# chassis_board.net
KiCad netlist of a schematic drawn in EAGLE
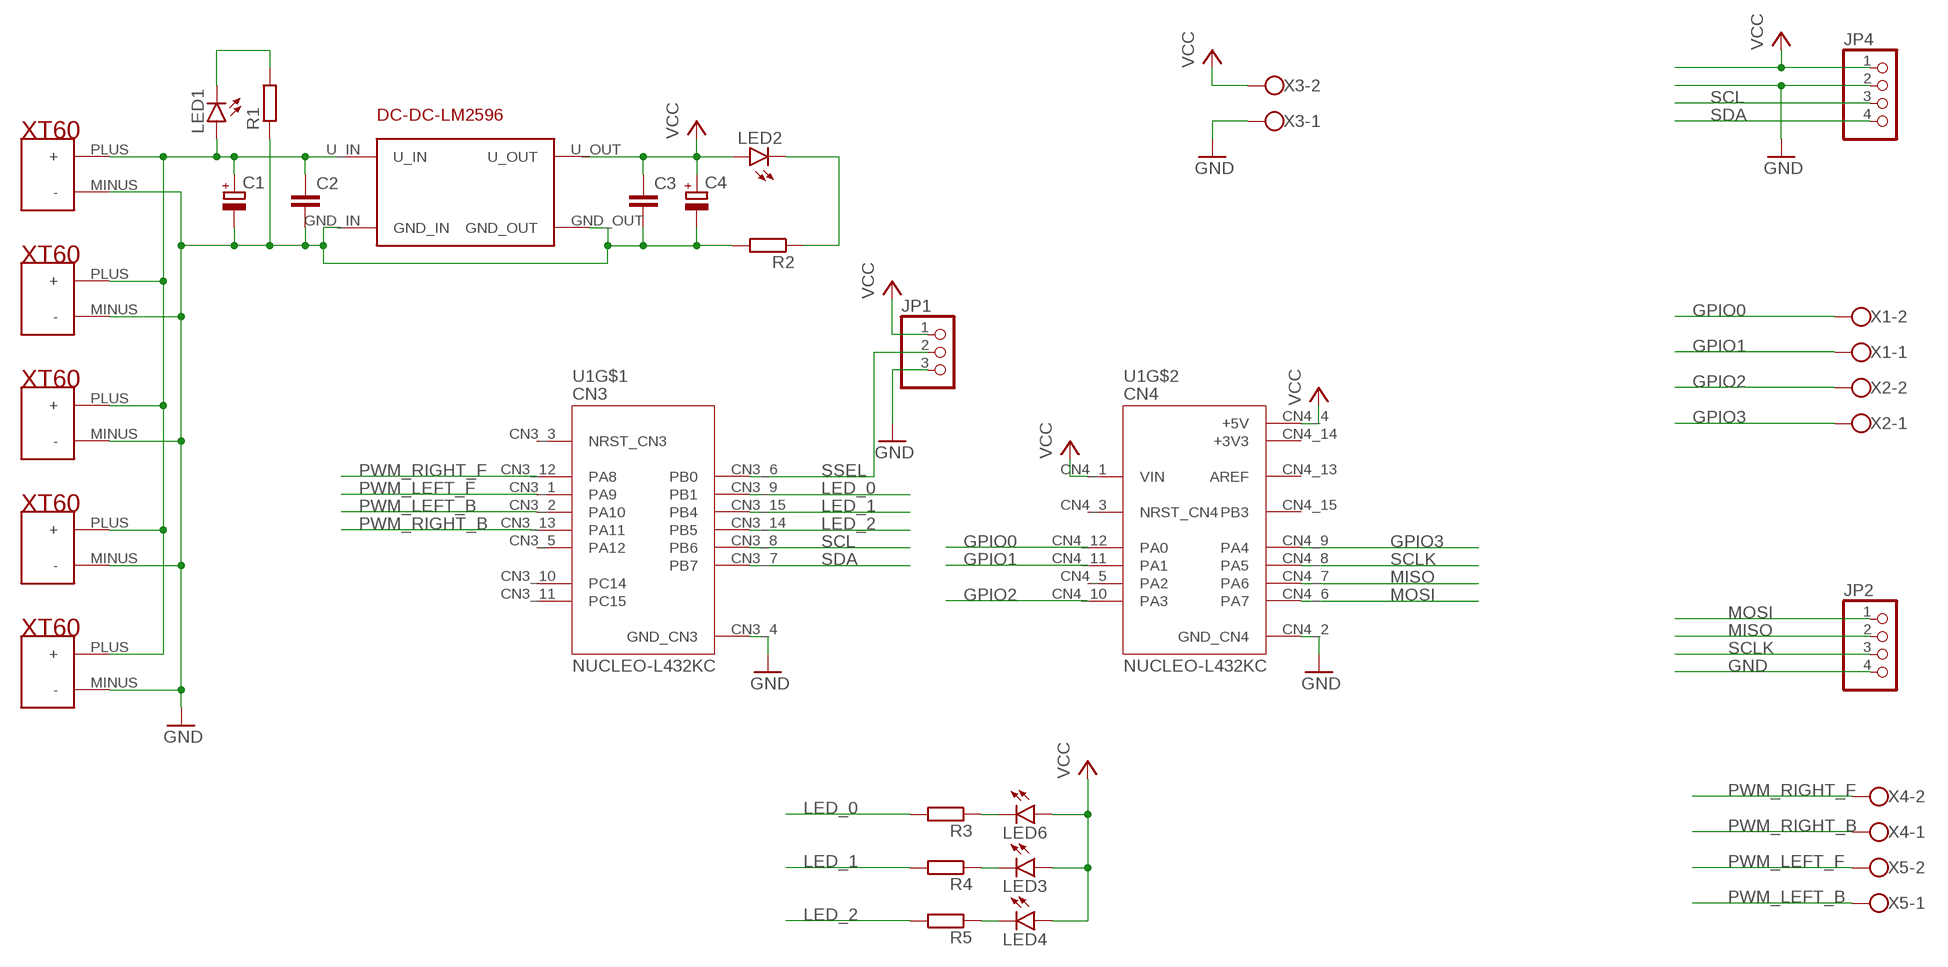
[diagram p0: schematic, sheet 1]

(export (version "E")
  (design (tool "Eeschema 10.0.6"))
  (components
    (comp (ref "C1")
      (value "CPOL-EU140CLH-0810")
      (footprint "eagle-import:140CLH-0810")
      (libsource (lib "eagle-import") (part "CPOL-EU140CLH-0810"))
    )
    (comp (ref "C2")
      (value "C-EUC1206")
      (footprint "eagle-import:C1206")
      (libsource (lib "eagle-import") (part "C-EUC1206"))
    )
    (comp (ref "C3")
      (value "C-EUC1206")
      (footprint "eagle-import:C1206")
      (libsource (lib "eagle-import") (part "C-EUC1206"))
    )
    (comp (ref "C4")
      (value "CPOL-EU140CLH-0810")
      (footprint "eagle-import:140CLH-0810")
      (libsource (lib "eagle-import") (part "CPOL-EU140CLH-0810"))
    )
    (comp (ref "JP1")
      (value "PINHD-1X3")
      (footprint "eagle-import:1X03")
      (libsource (lib "eagle-import") (part "PINHD-1X3"))
    )
    (comp (ref "JP2")
      (value "PINHD-1X4/90")
      (footprint "eagle-import:1X04_90")
      (libsource (lib "eagle-import") (part "PINHD-1X4/90"))
    )
    (comp (ref "JP4")
      (value "PINHD-1X4/90")
      (footprint "eagle-import:1X04_90")
      (libsource (lib "eagle-import") (part "PINHD-1X4/90"))
    )
    (comp (ref "LED1")
      (value "LEDSML1206")
      (footprint "eagle-import:SML1206")
      (libsource (lib "eagle-import") (part "LEDSML1206"))
    )
    (comp (ref "LED2")
      (value "LEDSML1206")
      (footprint "eagle-import:SML1206")
      (libsource (lib "eagle-import") (part "LEDSML1206"))
    )
    (comp (ref "LED3")
      (value "LEDSML1206")
      (footprint "eagle-import:SML1206")
      (libsource (lib "eagle-import") (part "LEDSML1206"))
    )
    (comp (ref "LED4")
      (value "LEDSML1206")
      (footprint "eagle-import:SML1206")
      (libsource (lib "eagle-import") (part "LEDSML1206"))
    )
    (comp (ref "LED6")
      (value "LEDSML1206")
      (footprint "eagle-import:SML1206")
      (libsource (lib "eagle-import") (part "LEDSML1206"))
    )
    (comp (ref "R1")
      (value "R-EU_M1206")
      (footprint "eagle-import:M1206")
      (libsource (lib "eagle-import") (part "R-EU_M1206"))
    )
    (comp (ref "R2")
      (value "R-EU_M1206")
      (footprint "eagle-import:M1206")
      (libsource (lib "eagle-import") (part "R-EU_M1206"))
    )
    (comp (ref "R3")
      (value "R-EU_M1206")
      (footprint "eagle-import:M1206")
      (libsource (lib "eagle-import") (part "R-EU_M1206"))
    )
    (comp (ref "R4")
      (value "R-EU_M1206")
      (footprint "eagle-import:M1206")
      (libsource (lib "eagle-import") (part "R-EU_M1206"))
    )
    (comp (ref "R5")
      (value "R-EU_M1206")
      (footprint "eagle-import:M1206")
      (libsource (lib "eagle-import") (part "R-EU_M1206"))
    )
    (comp (ref "U$1")
      (value "XT60")
      (footprint "eagle-import:XT60_FOOTPRINT")
      (libsource (lib "eagle-import") (part "XT60"))
    )
    (comp (ref "U$2")
      (value "XT60")
      (footprint "eagle-import:XT60_FOOTPRINT")
      (libsource (lib "eagle-import") (part "XT60"))
    )
    (comp (ref "U$3")
      (value "XT60")
      (footprint "eagle-import:XT60_FOOTPRINT")
      (libsource (lib "eagle-import") (part "XT60"))
    )
    (comp (ref "U$4")
      (value "XT60")
      (footprint "eagle-import:XT60_FOOTPRINT")
      (libsource (lib "eagle-import") (part "XT60"))
    )
    (comp (ref "U$5")
      (value "XT60")
      (footprint "eagle-import:XT60_FOOTPRINT")
      (libsource (lib "eagle-import") (part "XT60"))
    )
    (comp (ref "U$6")
      (value "DC-DC-LM2596")
      (footprint "eagle-import:DC-DC-LM2596")
      (libsource (lib "eagle-import") (part "DC-DC-LM2596"))
    )
    (comp (ref "U1")
      (value "NUCLEO-L432KC")
      (footprint "eagle-import:MODULE_NUCLEO-L432KC")
      (fields (field (name "MF") "STMicroelectronics"))
      (libsource (lib "eagle-import") (part "NUCLEO-L432KC"))
    )
    (comp (ref "X1")
      (value "W237-102")
      (footprint "eagle-import:W237-102")
      (fields (field (name "MPN") "237-102"))
      (libsource (lib "eagle-import") (part "W237-102"))
    )
    (comp (ref "X2")
      (value "W237-102")
      (footprint "eagle-import:W237-102")
      (fields (field (name "MPN") "237-102"))
      (libsource (lib "eagle-import") (part "W237-102"))
    )
    (comp (ref "X3")
      (value "W237-102")
      (footprint "eagle-import:W237-102")
      (fields (field (name "MPN") "237-102"))
      (libsource (lib "eagle-import") (part "W237-102"))
    )
    (comp (ref "X4")
      (value "W237-102")
      (footprint "eagle-import:W237-102")
      (fields (field (name "MPN") "237-102"))
      (libsource (lib "eagle-import") (part "W237-102"))
    )
    (comp (ref "X5")
      (value "W237-102")
      (footprint "eagle-import:W237-102")
      (fields (field (name "MPN") "237-102"))
      (libsource (lib "eagle-import") (part "W237-102"))
    )
  )
  (nets
    (net (code "1") (name "/+3V3") (class "Default")
      (node (ref "U1") (pin "CN4_14") (pinfunction "+3V3_CN4_14") (pintype "power_in"))
    )
    (net (code "2") (name "/GPIO0") (class "Default")
      (node (ref "U1") (pin "CN4_12") (pinfunction "PA0_CN4_12") (pintype "bidirectional"))
      (node (ref "X1") (pin "2") (pinfunction "KL_2") (pintype "passive"))
    )
    (net (code "3") (name "/GPIO1") (class "Default")
      (node (ref "U1") (pin "CN4_11") (pinfunction "PA1_CN4_11") (pintype "bidirectional"))
      (node (ref "X1") (pin "1") (pinfunction "KL_1") (pintype "passive"))
    )
    (net (code "4") (name "/GPIO2") (class "Default")
      (node (ref "U1") (pin "CN4_10") (pinfunction "PA3_CN4_10") (pintype "bidirectional"))
      (node (ref "X2") (pin "2") (pinfunction "KL_2") (pintype "passive"))
    )
    (net (code "5") (name "/GPIO3") (class "Default")
      (node (ref "U1") (pin "CN4_9") (pinfunction "PA4_CN4_9") (pintype "bidirectional"))
      (node (ref "X2") (pin "1") (pinfunction "KL_1") (pintype "passive"))
    )
    (net (code "6") (name "/LED_0") (class "Default")
      (node (ref "R3") (pin "2") (pinfunction "2_2") (pintype "passive"))
      (node (ref "U1") (pin "CN3_9") (pinfunction "PB1_CN3_9") (pintype "bidirectional"))
    )
    (net (code "7") (name "/LED_1") (class "Default")
      (node (ref "R4") (pin "2") (pinfunction "2_2") (pintype "passive"))
      (node (ref "U1") (pin "CN3_15") (pinfunction "PB4_CN3_15") (pintype "bidirectional"))
    )
    (net (code "8") (name "/LED_2") (class "Default")
      (node (ref "R5") (pin "2") (pinfunction "2_2") (pintype "passive"))
      (node (ref "U1") (pin "CN3_14") (pinfunction "PB5_CN3_14") (pintype "bidirectional"))
    )
    (net (code "9") (name "/MISO") (class "Default")
      (node (ref "JP2") (pin "2") (pinfunction "2_2") (pintype "passive"))
      (node (ref "U1") (pin "CN4_7") (pinfunction "PA6_CN4_7") (pintype "bidirectional"))
    )
    (net (code "10") (name "/MOSI") (class "Default")
      (node (ref "JP2") (pin "1") (pinfunction "1_1") (pintype "passive"))
      (node (ref "U1") (pin "CN4_6") (pinfunction "PA7_CN4_6") (pintype "bidirectional"))
    )
    (net (code "11") (name "/PWM_LEFT_B") (class "Default")
      (node (ref "U1") (pin "CN3_2") (pinfunction "PA10_CN3_2") (pintype "bidirectional"))
      (node (ref "X5") (pin "1") (pinfunction "KL_1") (pintype "passive"))
    )
    (net (code "12") (name "/PWM_LEFT_F") (class "Default")
      (node (ref "U1") (pin "CN3_1") (pinfunction "PA9_CN3_1") (pintype "bidirectional"))
      (node (ref "X5") (pin "2") (pinfunction "KL_2") (pintype "passive"))
    )
    (net (code "13") (name "/PWM_RIGHT_B") (class "Default")
      (node (ref "U1") (pin "CN3_13") (pinfunction "PA11_CN3_13") (pintype "bidirectional"))
      (node (ref "X4") (pin "1") (pinfunction "KL_1") (pintype "passive"))
    )
    (net (code "14") (name "/PWM_RIGHT_F") (class "Default")
      (node (ref "U1") (pin "CN3_12") (pinfunction "PA8_CN3_12") (pintype "bidirectional"))
      (node (ref "X4") (pin "2") (pinfunction "KL_2") (pintype "passive"))
    )
    (net (code "15") (name "/SCL") (class "Default")
      (node (ref "JP4") (pin "3") (pinfunction "3_3") (pintype "passive"))
      (node (ref "U1") (pin "CN3_8") (pinfunction "PB6_CN3_8") (pintype "bidirectional"))
    )
    (net (code "16") (name "/SCLK") (class "Default")
      (node (ref "JP2") (pin "3") (pinfunction "3_3") (pintype "passive"))
      (node (ref "U1") (pin "CN4_8") (pinfunction "PA5_CN4_8") (pintype "bidirectional"))
    )
    (net (code "17") (name "/SDA") (class "Default")
      (node (ref "JP4") (pin "4") (pinfunction "4_4") (pintype "passive"))
      (node (ref "U1") (pin "CN3_7") (pinfunction "PB7_CN3_7") (pintype "bidirectional"))
    )
    (net (code "18") (name "/SSEL") (class "Default")
      (node (ref "JP1") (pin "2") (pinfunction "2_2") (pintype "passive"))
      (node (ref "U1") (pin "CN3_6") (pinfunction "PB0_CN3_6") (pintype "bidirectional"))
    )
    (net (code "19") (name "GND") (class "Default")
      (node (ref "C1") (pin "-") (pinfunction "-_-") (pintype "passive"))
      (node (ref "C2") (pin "2") (pinfunction "2_2") (pintype "passive"))
      (node (ref "C3") (pin "2") (pinfunction "2_2") (pintype "passive"))
      (node (ref "C4") (pin "-") (pinfunction "-_-") (pintype "passive"))
      (node (ref "JP1") (pin "3") (pinfunction "3_3") (pintype "passive"))
      (node (ref "JP2") (pin "4") (pinfunction "4_4") (pintype "passive"))
      (node (ref "JP4") (pin "2") (pinfunction "2_2") (pintype "passive"))
      (node (ref "R1") (pin "1") (pinfunction "1_1") (pintype "passive"))
      (node (ref "R2") (pin "2") (pinfunction "2_2") (pintype "passive"))
      (node (ref "U$1") (pin "MINUS") (pinfunction "-_MINUS") (pintype "bidirectional"))
      (node (ref "U$2") (pin "MINUS") (pinfunction "-_MINUS") (pintype "bidirectional"))
      (node (ref "U$3") (pin "MINUS") (pinfunction "-_MINUS") (pintype "bidirectional"))
      (node (ref "U$4") (pin "MINUS") (pinfunction "-_MINUS") (pintype "bidirectional"))
      (node (ref "U$5") (pin "MINUS") (pinfunction "-_MINUS") (pintype "bidirectional"))
      (node (ref "U$6") (pin "GND_IN") (pinfunction "GND_IN_GND_IN") (pintype "bidirectional"))
      (node (ref "U$6") (pin "GND_OUT") (pinfunction "GND_OUT_GND_OUT") (pintype "bidirectional"))
      (node (ref "U1") (pin "CN3_4") (pinfunction "GND_CN3_CN3_4") (pintype "power_in"))
      (node (ref "U1") (pin "CN4_2") (pinfunction "GND_CN4_CN4_2") (pintype "power_in"))
      (node (ref "X3") (pin "1") (pinfunction "KL_1") (pintype "passive"))
    )
    (net (code "20") (name "Net-(LED1-PadC)") (class "Default")
      (node (ref "LED1") (pin "C") (pinfunction "C_C") (pintype "passive"))
      (node (ref "R1") (pin "2") (pinfunction "2_2") (pintype "passive"))
    )
    (net (code "21") (name "Net-(LED2-PadC)") (class "Default")
      (node (ref "LED2") (pin "C") (pinfunction "C_C") (pintype "passive"))
      (node (ref "R2") (pin "1") (pinfunction "1_1") (pintype "passive"))
    )
    (net (code "22") (name "Net-(LED3-PadC)") (class "Default")
      (node (ref "LED3") (pin "C") (pinfunction "C_C") (pintype "passive"))
      (node (ref "R4") (pin "1") (pinfunction "1_1") (pintype "passive"))
    )
    (net (code "23") (name "Net-(LED4-PadC)") (class "Default")
      (node (ref "LED4") (pin "C") (pinfunction "C_C") (pintype "passive"))
      (node (ref "R5") (pin "1") (pinfunction "1_1") (pintype "passive"))
    )
    (net (code "24") (name "Net-(LED6-PadC)") (class "Default")
      (node (ref "LED6") (pin "C") (pinfunction "C_C") (pintype "passive"))
      (node (ref "R3") (pin "1") (pinfunction "1_1") (pintype "passive"))
    )
    (net (code "25") (name "Net-(U$1-+)") (class "Default")
      (node (ref "C1") (pin "+") (pinfunction "+_+") (pintype "passive"))
      (node (ref "C2") (pin "1") (pinfunction "1_1") (pintype "passive"))
      (node (ref "LED1") (pin "A") (pinfunction "A_A") (pintype "passive"))
      (node (ref "U$1") (pin "PLUS") (pinfunction "+_PLUS") (pintype "bidirectional"))
      (node (ref "U$2") (pin "PLUS") (pinfunction "+_PLUS") (pintype "bidirectional"))
      (node (ref "U$3") (pin "PLUS") (pinfunction "+_PLUS") (pintype "bidirectional"))
      (node (ref "U$4") (pin "PLUS") (pinfunction "+_PLUS") (pintype "bidirectional"))
      (node (ref "U$5") (pin "PLUS") (pinfunction "+_PLUS") (pintype "bidirectional"))
      (node (ref "U$6") (pin "U_IN") (pinfunction "U_IN_U_IN") (pintype "bidirectional"))
    )
    (net (code "26") (name "VCC") (class "Default")
      (node (ref "C3") (pin "1") (pinfunction "1_1") (pintype "passive"))
      (node (ref "C4") (pin "+") (pinfunction "+_+") (pintype "passive"))
      (node (ref "JP1") (pin "1") (pinfunction "1_1") (pintype "passive"))
      (node (ref "JP4") (pin "1") (pinfunction "1_1") (pintype "passive"))
      (node (ref "LED2") (pin "A") (pinfunction "A_A") (pintype "passive"))
      (node (ref "LED3") (pin "A") (pinfunction "A_A") (pintype "passive"))
      (node (ref "LED4") (pin "A") (pinfunction "A_A") (pintype "passive"))
      (node (ref "LED6") (pin "A") (pinfunction "A_A") (pintype "passive"))
      (node (ref "U$6") (pin "U_OUT") (pinfunction "U_OUT_U_OUT") (pintype "bidirectional"))
      (node (ref "U1") (pin "CN4_1") (pinfunction "VIN_CN4_1") (pintype "input"))
      (node (ref "U1") (pin "CN4_4") (pinfunction "+5V_CN4_4") (pintype "power_in"))
      (node (ref "X3") (pin "2") (pinfunction "KL_2") (pintype "passive"))
    )
    (net (code "27") (name "unconnected-(U1A-NRST_CN3-PadCN3_3)") (class "Default")
      (node (ref "U1") (pin "CN3_3") (pinfunction "NRST_CN3_CN3_3") (pintype "bidirectional"))
    )
    (net (code "28") (name "unconnected-(U1A-PA12-PadCN3_5)") (class "Default")
      (node (ref "U1") (pin "CN3_5") (pinfunction "PA12_CN3_5") (pintype "bidirectional"))
    )
    (net (code "29") (name "unconnected-(U1A-PC14-PadCN3_10)") (class "Default")
      (node (ref "U1") (pin "CN3_10") (pinfunction "PC14_CN3_10") (pintype "bidirectional"))
    )
    (net (code "30") (name "unconnected-(U1A-PC15-PadCN3_11)") (class "Default")
      (node (ref "U1") (pin "CN3_11") (pinfunction "PC15_CN3_11") (pintype "bidirectional"))
    )
    (net (code "31") (name "unconnected-(U1B-AREF-PadCN4_13)") (class "Default")
      (node (ref "U1") (pin "CN4_13") (pinfunction "AREF_CN4_13") (pintype "bidirectional"))
    )
    (net (code "32") (name "unconnected-(U1B-NRST_CN4-PadCN4_3)") (class "Default")
      (node (ref "U1") (pin "CN4_3") (pinfunction "NRST_CN4_CN4_3") (pintype "bidirectional"))
    )
    (net (code "33") (name "unconnected-(U1B-PA2-PadCN4_5)") (class "Default")
      (node (ref "U1") (pin "CN4_5") (pinfunction "PA2_CN4_5") (pintype "bidirectional"))
    )
    (net (code "34") (name "unconnected-(U1B-PB3-PadCN4_15)") (class "Default")
      (node (ref "U1") (pin "CN4_15") (pinfunction "PB3_CN4_15") (pintype "bidirectional"))
    )
  )
)
